# ProductQ.net
KiCad netlist of a schematic drawn in EAGLE
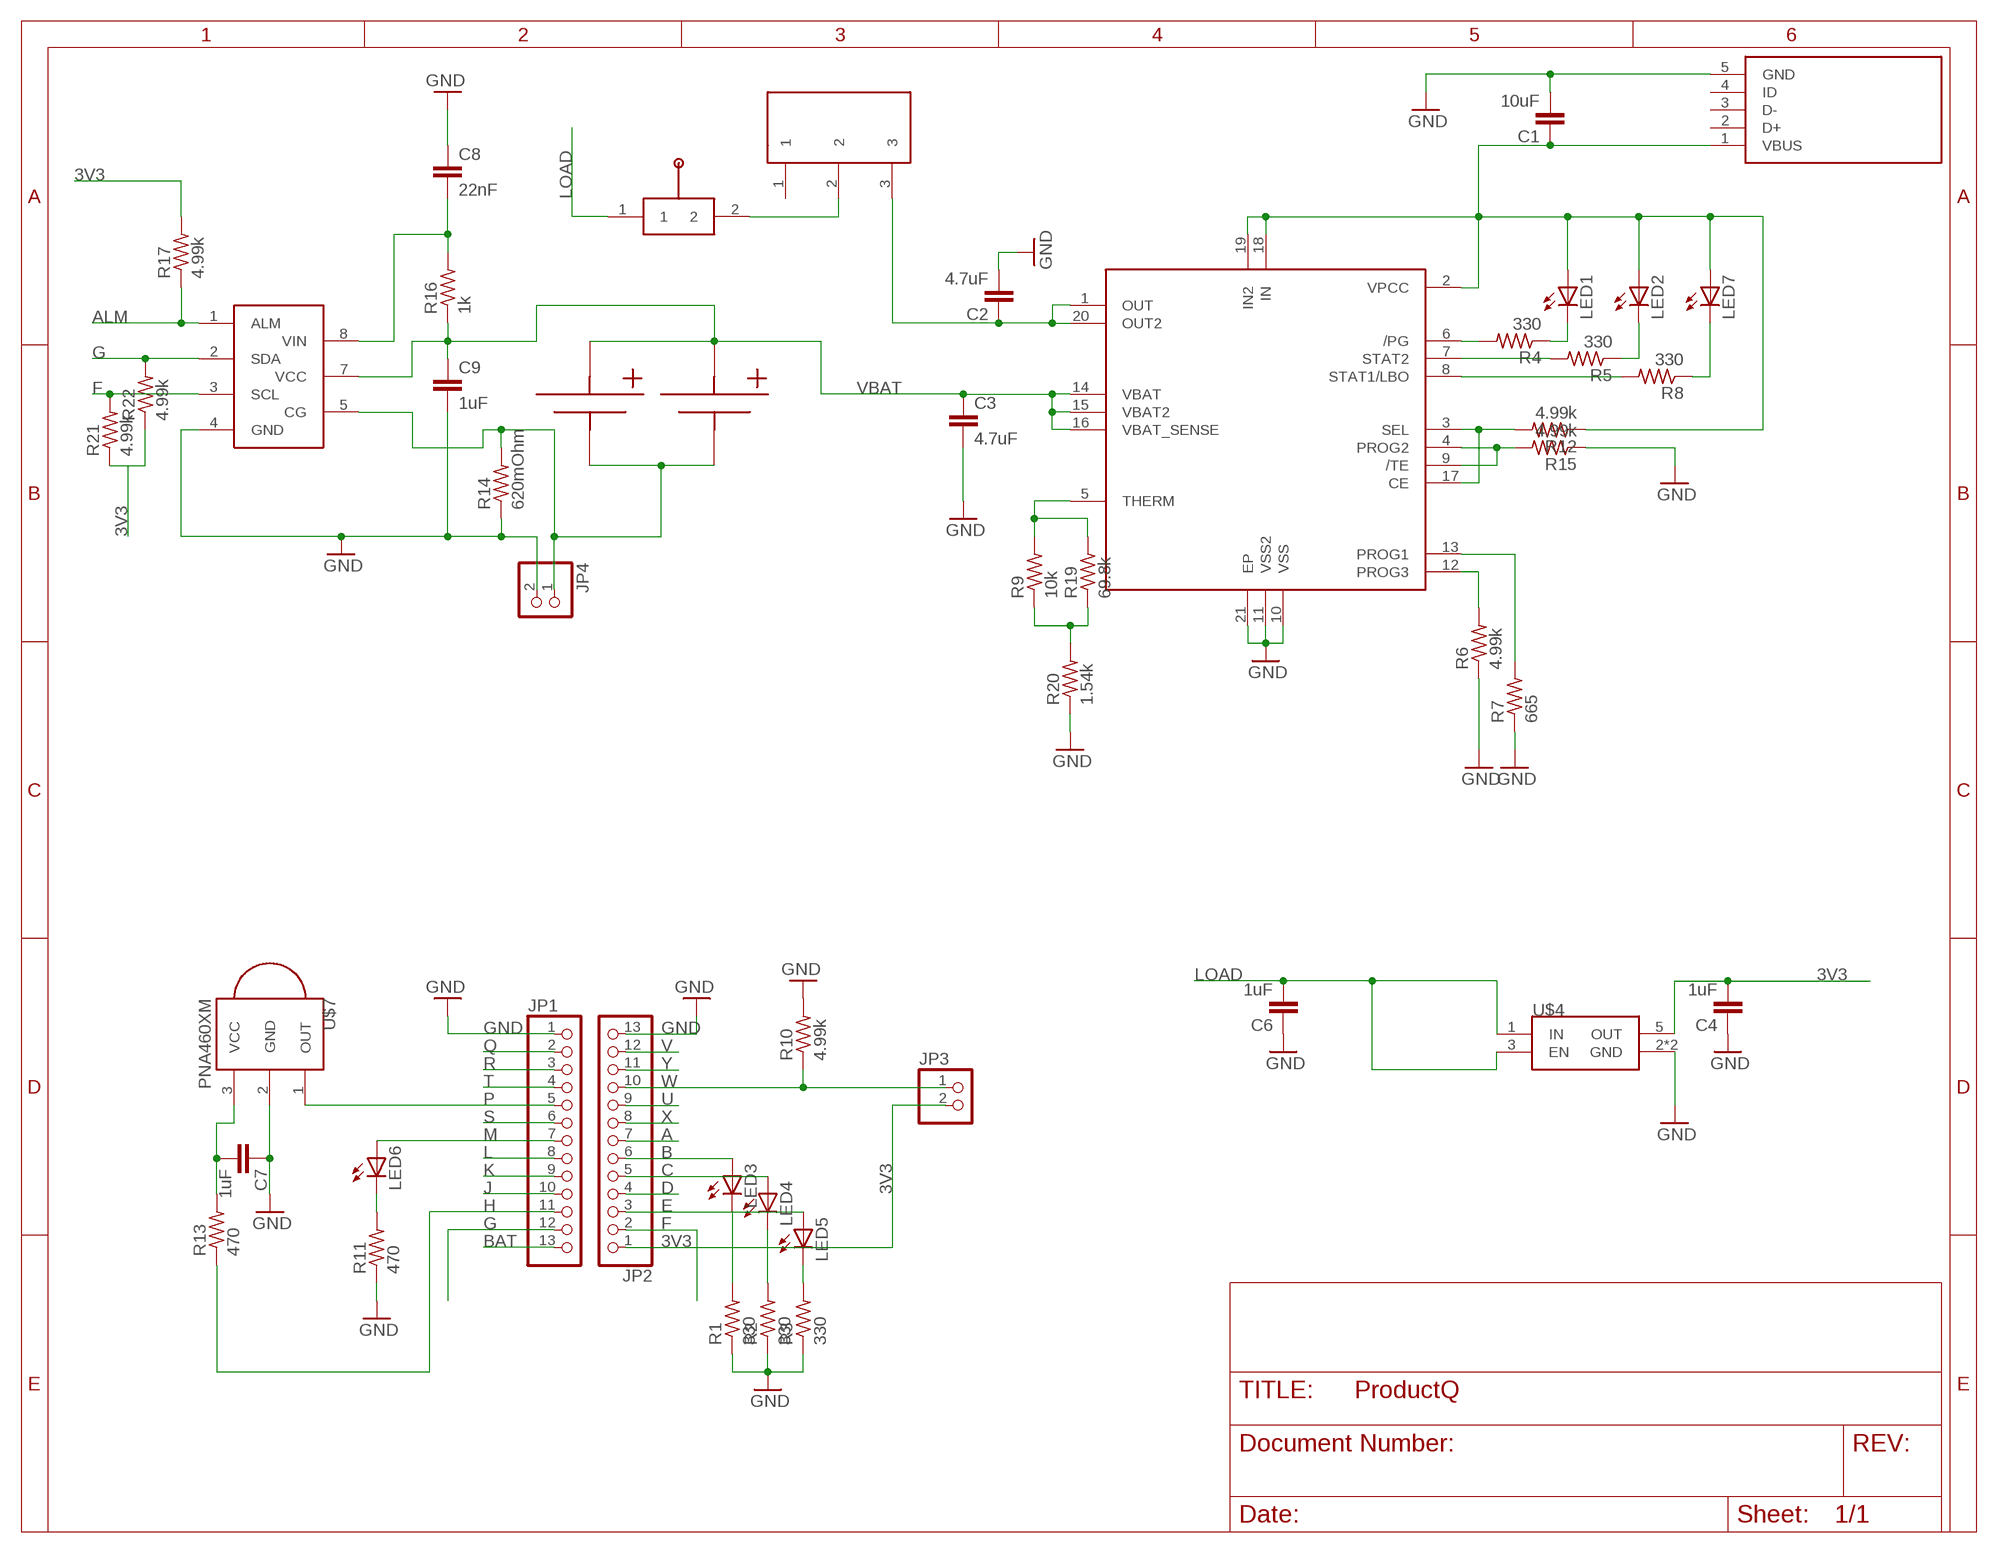
[diagram p0: schematic, sheet 1]

(export (version "E")
  (design (tool "Eeschema 10.0.6"))
  (components
    (comp (ref "C1")
      (value "10uF")
      (footprint "eagle-import:C0402")
      (libsource (lib "eagle-import") (part "C-EUC0402"))
    )
    (comp (ref "C2")
      (value "4.7uF")
      (footprint "eagle-import:C0402")
      (libsource (lib "eagle-import") (part "C-EUC0402"))
    )
    (comp (ref "C3")
      (value "4.7uF")
      (footprint "eagle-import:C0402")
      (libsource (lib "eagle-import") (part "C-EUC0402"))
    )
    (comp (ref "C4")
      (value "1uF")
      (footprint "eagle-import:C0402")
      (libsource (lib "eagle-import") (part "C-EUC0402"))
    )
    (comp (ref "C6")
      (value "1uF")
      (footprint "eagle-import:C0402")
      (libsource (lib "eagle-import") (part "C-EUC0402"))
    )
    (comp (ref "C7")
      (value "1uF")
      (footprint "eagle-import:C0402")
      (libsource (lib "eagle-import") (part "C-EUC0402"))
    )
    (comp (ref "C8")
      (value "22nF")
      (footprint "eagle-import:C0402")
      (libsource (lib "eagle-import") (part "C-EUC0402"))
    )
    (comp (ref "C9")
      (value "1uF")
      (footprint "eagle-import:C0402")
      (libsource (lib "eagle-import") (part "C-EUC0402"))
    )
    (comp (ref "JP1")
      (value "PINHD-1X13")
      (footprint "eagle-import:1X13")
      (libsource (lib "eagle-import") (part "PINHD-1X13"))
    )
    (comp (ref "JP2")
      (value "PINHD-1X13")
      (footprint "eagle-import:1X13")
      (libsource (lib "eagle-import") (part "PINHD-1X13"))
    )
    (comp (ref "JP3")
      (value "PINHD-1X2/90")
      (footprint "eagle-import:1X02_90")
      (libsource (lib "eagle-import") (part "PINHD-1X2/90"))
    )
    (comp (ref "JP4")
      (value "PINHD-1X2")
      (footprint "eagle-import:1X02")
      (libsource (lib "eagle-import") (part "PINHD-1X2"))
    )
    (comp (ref "LED1")
      (value "LEDCHIP-LED0805")
      (footprint "eagle-import:CHIP-LED0805")
      (libsource (lib "eagle-import") (part "LEDCHIP-LED0805"))
    )
    (comp (ref "LED2")
      (value "LEDCHIP-LED0805")
      (footprint "eagle-import:CHIP-LED0805")
      (libsource (lib "eagle-import") (part "LEDCHIP-LED0805"))
    )
    (comp (ref "LED3")
      (value "LEDCHIP-LED0805")
      (footprint "eagle-import:CHIP-LED0805")
      (libsource (lib "eagle-import") (part "LEDCHIP-LED0805"))
    )
    (comp (ref "LED4")
      (value "LEDCHIP-LED0805")
      (footprint "eagle-import:CHIP-LED0805")
      (libsource (lib "eagle-import") (part "LEDCHIP-LED0805"))
    )
    (comp (ref "LED5")
      (value "LEDCHIP-LED0805")
      (footprint "eagle-import:CHIP-LED0805")
      (libsource (lib "eagle-import") (part "LEDCHIP-LED0805"))
    )
    (comp (ref "LED6")
      (value "LED3MM")
      (footprint "eagle-import:LED3MM")
      (libsource (lib "eagle-import") (part "LED3MM"))
    )
    (comp (ref "LED7")
      (value "LEDCHIP-LED0805")
      (footprint "eagle-import:CHIP-LED0805")
      (libsource (lib "eagle-import") (part "LEDCHIP-LED0805"))
    )
    (comp (ref "R1")
      (value "330")
      (footprint "eagle-import:R0402")
      (libsource (lib "eagle-import") (part "R-US_R0402"))
    )
    (comp (ref "R2")
      (value "330")
      (footprint "eagle-import:R0402")
      (libsource (lib "eagle-import") (part "R-US_R0402"))
    )
    (comp (ref "R3")
      (value "330")
      (footprint "eagle-import:R0402")
      (libsource (lib "eagle-import") (part "R-US_R0402"))
    )
    (comp (ref "R4")
      (value "330")
      (footprint "eagle-import:R0402")
      (libsource (lib "eagle-import") (part "R-US_R0402"))
    )
    (comp (ref "R5")
      (value "330")
      (footprint "eagle-import:R0402")
      (libsource (lib "eagle-import") (part "R-US_R0402"))
    )
    (comp (ref "R6")
      (value "4.99k")
      (footprint "eagle-import:R0402")
      (libsource (lib "eagle-import") (part "R-US_R0402"))
    )
    (comp (ref "R7")
      (value "665")
      (footprint "eagle-import:R0402")
      (libsource (lib "eagle-import") (part "R-US_R0402"))
    )
    (comp (ref "R8")
      (value "330")
      (footprint "eagle-import:R0402")
      (libsource (lib "eagle-import") (part "R-US_R0402"))
    )
    (comp (ref "R9")
      (value "10k")
      (footprint "eagle-import:R0402")
      (libsource (lib "eagle-import") (part "R-US_R0402"))
    )
    (comp (ref "R10")
      (value "4.99k")
      (footprint "eagle-import:R0402")
      (libsource (lib "eagle-import") (part "R-US_R0402"))
    )
    (comp (ref "R11")
      (value "470")
      (footprint "eagle-import:R0402")
      (libsource (lib "eagle-import") (part "R-US_R0402"))
    )
    (comp (ref "R12")
      (value "4.99k")
      (footprint "eagle-import:R0402")
      (libsource (lib "eagle-import") (part "R-US_R0402"))
    )
    (comp (ref "R13")
      (value "470")
      (footprint "eagle-import:R0402")
      (libsource (lib "eagle-import") (part "R-US_R0402"))
    )
    (comp (ref "R14")
      (value "620mOhm")
      (footprint "eagle-import:R0603")
      (libsource (lib "eagle-import") (part "R-US_R0603"))
    )
    (comp (ref "R15")
      (value "4.99k")
      (footprint "eagle-import:R0402")
      (libsource (lib "eagle-import") (part "R-US_R0402"))
    )
    (comp (ref "R16")
      (value "1k")
      (footprint "eagle-import:R0402")
      (libsource (lib "eagle-import") (part "R-US_R0402"))
    )
    (comp (ref "R17")
      (value "4.99k")
      (footprint "eagle-import:R0402")
      (libsource (lib "eagle-import") (part "R-US_R0402"))
    )
    (comp (ref "R19")
      (value "69.8k")
      (footprint "eagle-import:R0402")
      (libsource (lib "eagle-import") (part "R-US_R0402"))
    )
    (comp (ref "R20")
      (value "1.54k")
      (footprint "eagle-import:R0402")
      (libsource (lib "eagle-import") (part "R-US_R0402"))
    )
    (comp (ref "R21")
      (value "4.99k")
      (footprint "eagle-import:R0402")
      (libsource (lib "eagle-import") (part "R-US_R0402"))
    )
    (comp (ref "R22")
      (value "4.99k")
      (footprint "eagle-import:R0402")
      (libsource (lib "eagle-import") (part "R-US_R0402"))
    )
    (comp (ref "U$1")
      (value "MCP73871")
      (footprint "eagle-import:QFN_20")
      (libsource (lib "eagle-import") (part "MCP73871"))
    )
    (comp (ref "U$2")
      (value "SPDT_THRU")
      (footprint "eagle-import:SPDT_THRU")
      (libsource (lib "eagle-import") (part "SPDT_THRU"))
    )
    (comp (ref "U$3")
      (value "USB_MINI")
      (footprint "eagle-import:USB_MINI")
      (libsource (lib "eagle-import") (part "USB_MINI"))
    )
    (comp (ref "U$4")
      (value "TPS782XX")
      (footprint "eagle-import:SOT23-5L")
      (libsource (lib "eagle-import") (part "TPS782XX"))
    )
    (comp (ref "U$5")
      (value "18650SMD")
      (footprint "eagle-import:18650KEYSTONE")
      (libsource (lib "eagle-import") (part "18650SMD"))
    )
    (comp (ref "U$6")
      (value "18650SMD")
      (footprint "eagle-import:18650KEYSTONE")
      (libsource (lib "eagle-import") (part "18650SMD"))
    )
    (comp (ref "U$7")
      (value "PNA460XM")
      (footprint "eagle-import:PNA460XM")
      (libsource (lib "eagle-import") (part "PNA460XM"))
    )
    (comp (ref "U$8")
      (value "STC3105")
      (footprint "eagle-import:STC3105")
      (libsource (lib "eagle-import") (part "STC3105"))
    )
    (comp (ref "U$9")
      (value "MANUAL_SWITCH")
      (footprint "eagle-import:MANUAL_SWITCH")
      (libsource (lib "eagle-import") (part "MANUAL_SWITCH"))
    )
  )
  (nets
    (net (code "1") (name "/3V3") (class "Default")
      (node (ref "C4") (pin "2") (pinfunction "2_2") (pintype "passive"))
      (node (ref "JP2") (pin "1") (pinfunction "1_1") (pintype "passive"))
      (node (ref "JP3") (pin "2") (pinfunction "2_2") (pintype "passive"))
      (node (ref "R17") (pin "2") (pinfunction "2_2") (pintype "passive"))
      (node (ref "R21") (pin "1") (pinfunction "1_1") (pintype "passive"))
      (node (ref "R22") (pin "1") (pinfunction "1_1") (pintype "passive"))
      (node (ref "U$4") (pin "5") (pinfunction "OUT_5") (pintype "bidirectional"))
    )
    (net (code "2") (name "/A") (class "Default")
      (node (ref "JP2") (pin "7") (pinfunction "7_7") (pintype "passive"))
    )
    (net (code "3") (name "/ALM") (class "Default")
      (node (ref "R17") (pin "1") (pinfunction "1_1") (pintype "passive"))
      (node (ref "U$8") (pin "1") (pinfunction "ALM_1") (pintype "bidirectional"))
    )
    (net (code "4") (name "/B") (class "Default")
      (node (ref "JP2") (pin "6") (pinfunction "6_6") (pintype "passive"))
      (node (ref "LED3") (pin "A") (pinfunction "A_A") (pintype "passive"))
    )
    (net (code "5") (name "/BAT") (class "Default")
      (node (ref "JP1") (pin "13") (pinfunction "13_13") (pintype "passive"))
    )
    (net (code "6") (name "/C") (class "Default")
      (node (ref "JP2") (pin "5") (pinfunction "5_5") (pintype "passive"))
      (node (ref "LED4") (pin "A") (pinfunction "A_A") (pintype "passive"))
    )
    (net (code "7") (name "/D") (class "Default")
      (node (ref "JP2") (pin "4") (pinfunction "4_4") (pintype "passive"))
    )
    (net (code "8") (name "/E") (class "Default")
      (node (ref "JP2") (pin "3") (pinfunction "3_3") (pintype "passive"))
      (node (ref "LED5") (pin "A") (pinfunction "A_A") (pintype "passive"))
    )
    (net (code "9") (name "/F") (class "Default")
      (node (ref "JP2") (pin "2") (pinfunction "2_2") (pintype "passive"))
      (node (ref "R21") (pin "2") (pinfunction "2_2") (pintype "passive"))
      (node (ref "U$8") (pin "3") (pinfunction "SCL_3") (pintype "bidirectional"))
    )
    (net (code "10") (name "/G") (class "Default")
      (node (ref "JP1") (pin "12") (pinfunction "12_12") (pintype "passive"))
      (node (ref "R22") (pin "2") (pinfunction "2_2") (pintype "passive"))
      (node (ref "U$8") (pin "2") (pinfunction "SDA_2") (pintype "bidirectional"))
    )
    (net (code "11") (name "/H") (class "Default")
      (node (ref "JP1") (pin "11") (pinfunction "11_11") (pintype "passive"))
      (node (ref "R13") (pin "1") (pinfunction "1_1") (pintype "passive"))
    )
    (net (code "12") (name "/J") (class "Default")
      (node (ref "JP1") (pin "10") (pinfunction "10_10") (pintype "passive"))
    )
    (net (code "13") (name "/K") (class "Default")
      (node (ref "JP1") (pin "9") (pinfunction "9_9") (pintype "passive"))
    )
    (net (code "14") (name "/L") (class "Default")
      (node (ref "JP1") (pin "8") (pinfunction "8_8") (pintype "passive"))
    )
    (net (code "15") (name "/LOAD") (class "Default")
      (node (ref "C6") (pin "2") (pinfunction "2_2") (pintype "passive"))
      (node (ref "U$4") (pin "1") (pinfunction "IN_1") (pintype "bidirectional"))
      (node (ref "U$4") (pin "3") (pinfunction "EN_3") (pintype "bidirectional"))
      (node (ref "U$9") (pin "1") (pinfunction "1_1") (pintype "bidirectional"))
    )
    (net (code "16") (name "/M") (class "Default")
      (node (ref "JP1") (pin "7") (pinfunction "7_7") (pintype "passive"))
      (node (ref "LED6") (pin "A") (pinfunction "A_A") (pintype "passive"))
    )
    (net (code "17") (name "/P") (class "Default")
      (node (ref "JP1") (pin "5") (pinfunction "5_5") (pintype "passive"))
      (node (ref "U$7") (pin "1") (pinfunction "OUT_1") (pintype "output"))
    )
    (net (code "18") (name "/Q") (class "Default")
      (node (ref "JP1") (pin "2") (pinfunction "2_2") (pintype "passive"))
    )
    (net (code "19") (name "/R") (class "Default")
      (node (ref "JP1") (pin "3") (pinfunction "3_3") (pintype "passive"))
    )
    (net (code "20") (name "/S") (class "Default")
      (node (ref "JP1") (pin "6") (pinfunction "6_6") (pintype "passive"))
    )
    (net (code "21") (name "/T") (class "Default")
      (node (ref "JP1") (pin "4") (pinfunction "4_4") (pintype "passive"))
    )
    (net (code "22") (name "/U") (class "Default")
      (node (ref "JP2") (pin "9") (pinfunction "9_9") (pintype "passive"))
    )
    (net (code "23") (name "/V") (class "Default")
      (node (ref "JP2") (pin "12") (pinfunction "12_12") (pintype "passive"))
    )
    (net (code "24") (name "/VBAT") (class "Default")
      (node (ref "C3") (pin "1") (pinfunction "1_1") (pintype "passive"))
      (node (ref "C9") (pin "1") (pinfunction "1_1") (pintype "passive"))
      (node (ref "R16") (pin "1") (pinfunction "1_1") (pintype "passive"))
      (node (ref "U$1") (pin "14") (pinfunction "VBAT_14") (pintype "bidirectional"))
      (node (ref "U$1") (pin "15") (pinfunction "VBAT2_15") (pintype "bidirectional"))
      (node (ref "U$1") (pin "16") (pinfunction "VBAT_SENSE_16") (pintype "bidirectional"))
      (node (ref "U$5") (pin "P$1") (pinfunction "P$1_P$1") (pintype "bidirectional"))
      (node (ref "U$6") (pin "P$1") (pinfunction "P$1_P$1") (pintype "bidirectional"))
      (node (ref "U$8") (pin "7") (pinfunction "VCC_7") (pintype "bidirectional"))
    )
    (net (code "25") (name "/W") (class "Default")
      (node (ref "JP2") (pin "10") (pinfunction "10_10") (pintype "passive"))
      (node (ref "JP3") (pin "1") (pinfunction "1_1") (pintype "passive"))
      (node (ref "R10") (pin "1") (pinfunction "1_1") (pintype "passive"))
    )
    (net (code "26") (name "/X") (class "Default")
      (node (ref "JP2") (pin "8") (pinfunction "8_8") (pintype "passive"))
    )
    (net (code "27") (name "/Y") (class "Default")
      (node (ref "JP2") (pin "11") (pinfunction "11_11") (pintype "passive"))
    )
    (net (code "28") (name "GND") (class "Default")
      (node (ref "C1") (pin "2") (pinfunction "2_2") (pintype "passive"))
      (node (ref "C2") (pin "2") (pinfunction "2_2") (pintype "passive"))
      (node (ref "C3") (pin "2") (pinfunction "2_2") (pintype "passive"))
      (node (ref "C4") (pin "1") (pinfunction "1_1") (pintype "passive"))
      (node (ref "C6") (pin "1") (pinfunction "1_1") (pintype "passive"))
      (node (ref "C7") (pin "1") (pinfunction "1_1") (pintype "passive"))
      (node (ref "C8") (pin "1") (pinfunction "1_1") (pintype "passive"))
      (node (ref "C9") (pin "2") (pinfunction "2_2") (pintype "passive"))
      (node (ref "JP1") (pin "1") (pinfunction "1_1") (pintype "passive"))
      (node (ref "JP2") (pin "13") (pinfunction "13_13") (pintype "passive"))
      (node (ref "JP4") (pin "2") (pinfunction "2_2") (pintype "passive"))
      (node (ref "R1") (pin "1") (pinfunction "1_1") (pintype "passive"))
      (node (ref "R10") (pin "2") (pinfunction "2_2") (pintype "passive"))
      (node (ref "R11") (pin "1") (pinfunction "1_1") (pintype "passive"))
      (node (ref "R14") (pin "1") (pinfunction "1_1") (pintype "passive"))
      (node (ref "R15") (pin "1") (pinfunction "1_1") (pintype "passive"))
      (node (ref "R2") (pin "1") (pinfunction "1_1") (pintype "passive"))
      (node (ref "R20") (pin "1") (pinfunction "1_1") (pintype "passive"))
      (node (ref "R3") (pin "1") (pinfunction "1_1") (pintype "passive"))
      (node (ref "R6") (pin "1") (pinfunction "1_1") (pintype "passive"))
      (node (ref "R7") (pin "1") (pinfunction "1_1") (pintype "passive"))
      (node (ref "U$1") (pin "10") (pinfunction "VSS_10") (pintype "bidirectional"))
      (node (ref "U$1") (pin "11") (pinfunction "VSS2_11") (pintype "bidirectional"))
      (node (ref "U$1") (pin "21") (pinfunction "EP_21") (pintype "bidirectional"))
      (node (ref "U$3") (pin "5") (pinfunction "GND_5") (pintype "bidirectional"))
      (node (ref "U$4") (pin "2") (pinfunction "GND_2") (pintype "bidirectional"))
      (node (ref "U$4") (pin "4") (pinfunction "GND_4") (pintype "bidirectional"))
      (node (ref "U$7") (pin "2") (pinfunction "GND_2") (pintype "power_in"))
      (node (ref "U$8") (pin "4") (pinfunction "GND_4") (pintype "bidirectional"))
    )
    (net (code "29") (name "Net-(LED1-PadC)") (class "Default")
      (node (ref "LED1") (pin "C") (pinfunction "C_C") (pintype "passive"))
      (node (ref "R4") (pin "1") (pinfunction "1_1") (pintype "passive"))
    )
    (net (code "30") (name "Net-(LED2-PadC)") (class "Default")
      (node (ref "LED2") (pin "C") (pinfunction "C_C") (pintype "passive"))
      (node (ref "R5") (pin "1") (pinfunction "1_1") (pintype "passive"))
    )
    (net (code "31") (name "Net-(LED3-PadC)") (class "Default")
      (node (ref "LED3") (pin "C") (pinfunction "C_C") (pintype "passive"))
      (node (ref "R1") (pin "2") (pinfunction "2_2") (pintype "passive"))
    )
    (net (code "32") (name "Net-(LED4-PadC)") (class "Default")
      (node (ref "LED4") (pin "C") (pinfunction "C_C") (pintype "passive"))
      (node (ref "R2") (pin "2") (pinfunction "2_2") (pintype "passive"))
    )
    (net (code "33") (name "Net-(LED5-PadC)") (class "Default")
      (node (ref "LED5") (pin "C") (pinfunction "C_C") (pintype "passive"))
      (node (ref "R3") (pin "2") (pinfunction "2_2") (pintype "passive"))
    )
    (net (code "34") (name "Net-(LED6-C)") (class "Default")
      (node (ref "LED6") (pin "K") (pinfunction "C_K") (pintype "passive"))
      (node (ref "R11") (pin "2") (pinfunction "2_2") (pintype "passive"))
    )
    (net (code "35") (name "Net-(LED7-PadC)") (class "Default")
      (node (ref "LED7") (pin "C") (pinfunction "C_C") (pintype "passive"))
      (node (ref "R8") (pin "1") (pinfunction "1_1") (pintype "passive"))
    )
    (net (code "36") (name "Net-(R19-Pad1)") (class "Default")
      (node (ref "R19") (pin "1") (pinfunction "1_1") (pintype "passive"))
      (node (ref "R20") (pin "2") (pinfunction "2_2") (pintype "passive"))
      (node (ref "R9") (pin "1") (pinfunction "1_1") (pintype "passive"))
    )
    (net (code "37") (name "Net-(U$1-CE)") (class "Default")
      (node (ref "R12") (pin "2") (pinfunction "2_2") (pintype "passive"))
      (node (ref "U$1") (pin "17") (pinfunction "CE_17") (pintype "bidirectional"))
      (node (ref "U$1") (pin "3") (pinfunction "SEL_3") (pintype "bidirectional"))
    )
    (net (code "38") (name "Net-(U$1-IN)") (class "Default")
      (node (ref "C1") (pin "1") (pinfunction "1_1") (pintype "passive"))
      (node (ref "LED1") (pin "A") (pinfunction "A_A") (pintype "passive"))
      (node (ref "LED2") (pin "A") (pinfunction "A_A") (pintype "passive"))
      (node (ref "LED7") (pin "A") (pinfunction "A_A") (pintype "passive"))
      (node (ref "R12") (pin "1") (pinfunction "1_1") (pintype "passive"))
      (node (ref "U$1") (pin "18") (pinfunction "IN_18") (pintype "bidirectional"))
      (node (ref "U$1") (pin "19") (pinfunction "IN2_19") (pintype "bidirectional"))
      (node (ref "U$1") (pin "2") (pinfunction "VPCC_2") (pintype "bidirectional"))
      (node (ref "U$3") (pin "1") (pinfunction "VBUS_1") (pintype "bidirectional"))
    )
    (net (code "39") (name "Net-(U$1-OUT)") (class "Default")
      (node (ref "C2") (pin "1") (pinfunction "1_1") (pintype "passive"))
      (node (ref "U$1") (pin "1") (pinfunction "OUT_1") (pintype "bidirectional"))
      (node (ref "U$1") (pin "20") (pinfunction "OUT2_20") (pintype "bidirectional"))
      (node (ref "U$2") (pin "3") (pinfunction "3_3") (pintype "bidirectional"))
    )
    (net (code "40") (name "Net-(U$1-PROG1)") (class "Default")
      (node (ref "R7") (pin "2") (pinfunction "2_2") (pintype "passive"))
      (node (ref "U$1") (pin "13") (pinfunction "PROG1_13") (pintype "bidirectional"))
    )
    (net (code "41") (name "Net-(U$1-PROG2)") (class "Default")
      (node (ref "R15") (pin "2") (pinfunction "2_2") (pintype "passive"))
      (node (ref "U$1") (pin "4") (pinfunction "PROG2_4") (pintype "bidirectional"))
      (node (ref "U$1") (pin "9") (pinfunction "/TE_9") (pintype "bidirectional"))
    )
    (net (code "42") (name "Net-(U$1-PROG3)") (class "Default")
      (node (ref "R6") (pin "2") (pinfunction "2_2") (pintype "passive"))
      (node (ref "U$1") (pin "12") (pinfunction "PROG3_12") (pintype "bidirectional"))
    )
    (net (code "43") (name "Net-(U$1-STAT1{slash}LBO)") (class "Default")
      (node (ref "R8") (pin "2") (pinfunction "2_2") (pintype "passive"))
      (node (ref "U$1") (pin "8") (pinfunction "STAT1/LBO_8") (pintype "bidirectional"))
    )
    (net (code "44") (name "Net-(U$1-STAT2)") (class "Default")
      (node (ref "R5") (pin "2") (pinfunction "2_2") (pintype "passive"))
      (node (ref "U$1") (pin "7") (pinfunction "STAT2_7") (pintype "bidirectional"))
    )
    (net (code "45") (name "Net-(U$1-THERM)") (class "Default")
      (node (ref "R19") (pin "2") (pinfunction "2_2") (pintype "passive"))
      (node (ref "R9") (pin "2") (pinfunction "2_2") (pintype "passive"))
      (node (ref "U$1") (pin "5") (pinfunction "THERM_5") (pintype "bidirectional"))
    )
    (net (code "46") (name "Net-(U$1-{slash}PG)") (class "Default")
      (node (ref "R4") (pin "2") (pinfunction "2_2") (pintype "passive"))
      (node (ref "U$1") (pin "6") (pinfunction "/PG_6") (pintype "bidirectional"))
    )
    (net (code "47") (name "Net-(U$2-Pad2)") (class "Default")
      (node (ref "U$2") (pin "2") (pinfunction "2_2") (pintype "bidirectional"))
      (node (ref "U$9") (pin "2") (pinfunction "2_2") (pintype "bidirectional"))
    )
    (net (code "48") (name "Net-(U$7-VCC)") (class "Default")
      (node (ref "C7") (pin "2") (pinfunction "2_2") (pintype "passive"))
      (node (ref "R13") (pin "2") (pinfunction "2_2") (pintype "passive"))
      (node (ref "U$7") (pin "3") (pinfunction "VCC_3") (pintype "power_in"))
    )
    (net (code "49") (name "Net-(U$8-CG)") (class "Default")
      (node (ref "JP4") (pin "1") (pinfunction "1_1") (pintype "passive"))
      (node (ref "R14") (pin "2") (pinfunction "2_2") (pintype "passive"))
      (node (ref "U$5") (pin "P$2") (pinfunction "P$2_P$2") (pintype "bidirectional"))
      (node (ref "U$6") (pin "P$2") (pinfunction "P$2_P$2") (pintype "bidirectional"))
      (node (ref "U$8") (pin "5") (pinfunction "CG_5") (pintype "bidirectional"))
    )
    (net (code "50") (name "Net-(U$8-VIN)") (class "Default")
      (node (ref "C8") (pin "2") (pinfunction "2_2") (pintype "passive"))
      (node (ref "R16") (pin "2") (pinfunction "2_2") (pintype "passive"))
      (node (ref "U$8") (pin "8") (pinfunction "VIN_8") (pintype "bidirectional"))
    )
    (net (code "51") (name "unconnected-(U$2-Pad1)") (class "Default")
      (node (ref "U$2") (pin "1") (pinfunction "1_1") (pintype "bidirectional"))
    )
    (net (code "52") (name "unconnected-(U$3-D+-Pad2)") (class "Default")
      (node (ref "U$3") (pin "2") (pinfunction "D+_2") (pintype "bidirectional"))
    )
    (net (code "53") (name "unconnected-(U$3-D--Pad3)") (class "Default")
      (node (ref "U$3") (pin "3") (pinfunction "D-_3") (pintype "bidirectional"))
    )
    (net (code "54") (name "unconnected-(U$3-ID-Pad4)") (class "Default")
      (node (ref "U$3") (pin "4") (pinfunction "ID_4") (pintype "bidirectional"))
    )
  )
)
